# darklamp.net
KiCad netlist of a schematic drawn in EAGLE
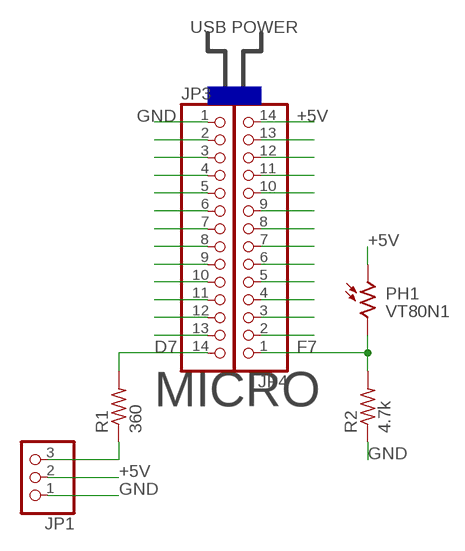
[diagram p0: schematic, sheet 1]

(export (version "E")
  (design (tool "Eeschema 10.0.6"))
  (components
    (comp (ref "JP1")
      (value "PINHD-1X3")
      (footprint "eagle-import:1X03")
      (libsource (lib "eagle-import") (part "PINHD-1X3"))
    )
    (comp (ref "JP3")
      (value "PINHD-1X14")
      (footprint "eagle-import:1X14")
      (libsource (lib "eagle-import") (part "PINHD-1X14"))
    )
    (comp (ref "JP4")
      (value "PINHD-1X14")
      (footprint "eagle-import:1X14")
      (libsource (lib "eagle-import") (part "PINHD-1X14"))
    )
    (comp (ref "PH1")
      (value "VT80N1")
      (footprint "eagle-import:VT800")
      (libsource (lib "eagle-import") (part "VT80N1"))
    )
    (comp (ref "R1")
      (value "360")
      (footprint "eagle-import:0204V")
      (libsource (lib "eagle-import") (part "R-US_0204/2V"))
    )
    (comp (ref "R2")
      (value "4.7k")
      (footprint "eagle-import:0204V")
      (libsource (lib "eagle-import") (part "R-US_0204/2V"))
    )
  )
  (nets
    (net (code "1") (name "/+5V") (class "Default")
      (node (ref "JP1") (pin "2") (pinfunction "2_2") (pintype "passive"))
      (node (ref "JP4") (pin "14") (pinfunction "14_14") (pintype "passive"))
      (node (ref "PH1") (pin "1") (pinfunction "1_1") (pintype "passive"))
    )
    (net (code "2") (name "/D7") (class "Default")
      (node (ref "JP3") (pin "14") (pinfunction "14_14") (pintype "passive"))
      (node (ref "R1") (pin "2") (pinfunction "2_2") (pintype "passive"))
    )
    (net (code "3") (name "/F7") (class "Default")
      (node (ref "JP4") (pin "1") (pinfunction "1_1") (pintype "passive"))
      (node (ref "PH1") (pin "2") (pinfunction "2_2") (pintype "passive"))
      (node (ref "R2") (pin "2") (pinfunction "2_2") (pintype "passive"))
    )
    (net (code "4") (name "/GND") (class "Default")
      (node (ref "JP1") (pin "1") (pinfunction "1_1") (pintype "passive"))
      (node (ref "JP3") (pin "1") (pinfunction "1_1") (pintype "passive"))
      (node (ref "R2") (pin "1") (pinfunction "1_1") (pintype "passive"))
    )
    (net (code "5") (name "Net-(JP1-Pad3)") (class "Default")
      (node (ref "JP1") (pin "3") (pinfunction "3_3") (pintype "passive"))
      (node (ref "R1") (pin "1") (pinfunction "1_1") (pintype "passive"))
    )
    (net (code "6") (name "unconnected-(JP3-Pad2)") (class "Default")
      (node (ref "JP3") (pin "2") (pinfunction "2_2") (pintype "passive"))
    )
    (net (code "7") (name "unconnected-(JP3-Pad3)") (class "Default")
      (node (ref "JP3") (pin "3") (pinfunction "3_3") (pintype "passive"))
    )
    (net (code "8") (name "unconnected-(JP3-Pad4)") (class "Default")
      (node (ref "JP3") (pin "4") (pinfunction "4_4") (pintype "passive"))
    )
    (net (code "9") (name "unconnected-(JP3-Pad5)") (class "Default")
      (node (ref "JP3") (pin "5") (pinfunction "5_5") (pintype "passive"))
    )
    (net (code "10") (name "unconnected-(JP3-Pad6)") (class "Default")
      (node (ref "JP3") (pin "6") (pinfunction "6_6") (pintype "passive"))
    )
    (net (code "11") (name "unconnected-(JP3-Pad7)") (class "Default")
      (node (ref "JP3") (pin "7") (pinfunction "7_7") (pintype "passive"))
    )
    (net (code "12") (name "unconnected-(JP3-Pad8)") (class "Default")
      (node (ref "JP3") (pin "8") (pinfunction "8_8") (pintype "passive"))
    )
    (net (code "13") (name "unconnected-(JP3-Pad9)") (class "Default")
      (node (ref "JP3") (pin "9") (pinfunction "9_9") (pintype "passive"))
    )
    (net (code "14") (name "unconnected-(JP3-Pad10)") (class "Default")
      (node (ref "JP3") (pin "10") (pinfunction "10_10") (pintype "passive"))
    )
    (net (code "15") (name "unconnected-(JP3-Pad11)") (class "Default")
      (node (ref "JP3") (pin "11") (pinfunction "11_11") (pintype "passive"))
    )
    (net (code "16") (name "unconnected-(JP3-Pad12)") (class "Default")
      (node (ref "JP3") (pin "12") (pinfunction "12_12") (pintype "passive"))
    )
    (net (code "17") (name "unconnected-(JP3-Pad13)") (class "Default")
      (node (ref "JP3") (pin "13") (pinfunction "13_13") (pintype "passive"))
    )
    (net (code "18") (name "unconnected-(JP4-Pad2)") (class "Default")
      (node (ref "JP4") (pin "2") (pinfunction "2_2") (pintype "passive"))
    )
    (net (code "19") (name "unconnected-(JP4-Pad3)") (class "Default")
      (node (ref "JP4") (pin "3") (pinfunction "3_3") (pintype "passive"))
    )
    (net (code "20") (name "unconnected-(JP4-Pad4)") (class "Default")
      (node (ref "JP4") (pin "4") (pinfunction "4_4") (pintype "passive"))
    )
    (net (code "21") (name "unconnected-(JP4-Pad5)") (class "Default")
      (node (ref "JP4") (pin "5") (pinfunction "5_5") (pintype "passive"))
    )
    (net (code "22") (name "unconnected-(JP4-Pad6)") (class "Default")
      (node (ref "JP4") (pin "6") (pinfunction "6_6") (pintype "passive"))
    )
    (net (code "23") (name "unconnected-(JP4-Pad7)") (class "Default")
      (node (ref "JP4") (pin "7") (pinfunction "7_7") (pintype "passive"))
    )
    (net (code "24") (name "unconnected-(JP4-Pad8)") (class "Default")
      (node (ref "JP4") (pin "8") (pinfunction "8_8") (pintype "passive"))
    )
    (net (code "25") (name "unconnected-(JP4-Pad9)") (class "Default")
      (node (ref "JP4") (pin "9") (pinfunction "9_9") (pintype "passive"))
    )
    (net (code "26") (name "unconnected-(JP4-Pad10)") (class "Default")
      (node (ref "JP4") (pin "10") (pinfunction "10_10") (pintype "passive"))
    )
    (net (code "27") (name "unconnected-(JP4-Pad11)") (class "Default")
      (node (ref "JP4") (pin "11") (pinfunction "11_11") (pintype "passive"))
    )
    (net (code "28") (name "unconnected-(JP4-Pad12)") (class "Default")
      (node (ref "JP4") (pin "12") (pinfunction "12_12") (pintype "passive"))
    )
    (net (code "29") (name "unconnected-(JP4-Pad13)") (class "Default")
      (node (ref "JP4") (pin "13") (pinfunction "13_13") (pintype "passive"))
    )
  )
)
